# Transistors.net
KiCad netlist of a schematic drawn in Altium Designer
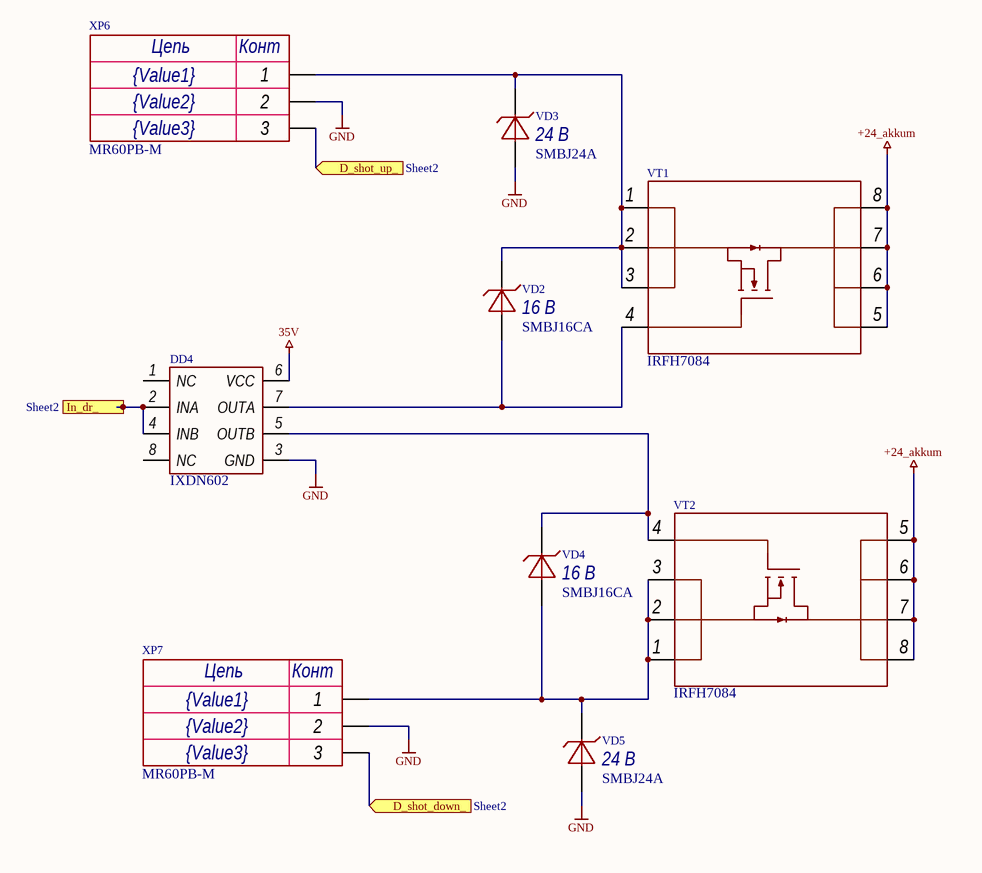
[diagram p0: Transistors.SchDoc]

(export (version "E")
  (design (tool "Eeschema 10.0.6"))
  (components
    (comp (ref "DD4")
      (value "IXDN602")
      (footprint "SOIC-8")
      (description "Двухканальный драйвер затвора для mosfet и igbt транзисторов")
      (libsource (lib "Hydrolib") (part "IXDN602"))
    )
    (comp (ref "VD2")
      (value "SMBJ16CA")
      (footprint "SMB")
      (description "Защитный диод двунаправленный 600Вт 16В")
      (fields (field (name "ALTIUM_VALUE") "16 В"))
      (libsource (lib "Hydrolib") (part "TVS_1_1dir"))
    )
    (comp (ref "VD3")
      (value "SMBJ24A")
      (footprint "SMB")
      (description "Защитный диод на 24 В, рассеиваемая мощность 600 Вт")
      (fields (field (name "ALTIUM_VALUE") "24 В"))
      (libsource (lib "Hydrolib") (part "TVS_1_1dir"))
    )
    (comp (ref "VD4")
      (value "SMBJ16CA")
      (footprint "SMB")
      (description "Защитный диод двунаправленный 600Вт 16В")
      (fields (field (name "ALTIUM_VALUE") "16 В"))
      (libsource (lib "Hydrolib") (part "TVS_1_1dir"))
    )
    (comp (ref "VD5")
      (value "SMBJ24A")
      (footprint "SMB")
      (description "Защитный диод на 24 В, рассеиваемая мощность 600 Вт")
      (fields (field (name "ALTIUM_VALUE") "24 В"))
      (libsource (lib "Hydrolib") (part "TVS_1_1dir"))
    )
    (comp (ref "VT1")
      (value "IRFH7084")
      (footprint "PQFN_5x6")
      (description "N-канальный MOSFET")
      (libsource (lib "") (part "MOSFET_N-channel_8pin_1"))
    )
    (comp (ref "VT2")
      (value "IRFH7084")
      (footprint "PQFN_5x6")
      (description "N-канальный MOSFET")
      (libsource (lib "Hydrolib") (part "MOSFET_N-channel_8pin"))
    )
    (comp (ref "XP6")
      (value "MR60PB-M")
      (footprint "MR60PB-M")
      (description "60 А (40 продолжительно), 3 контакта, прямой отец")
      (fields
        (field (name "VALUE3") "{Value3}")
        (field (name "VALUE2") "{Value2}")
        (field (name "VALUE1") "{Value1}")
      )
      (libsource (lib "Hydrolib") (part "Conn_3pin"))
    )
    (comp (ref "XP7")
      (value "MR60PB-M")
      (footprint "MR60PB-M")
      (description "60 А (40 продолжительно), 3 контакта, прямой отец")
      (fields
        (field (name "VALUE3") "{Value3}")
        (field (name "VALUE2") "{Value2}")
        (field (name "VALUE1") "{Value1}")
      )
      (libsource (lib "Hydrolib") (part "Conn_3pin"))
    )
  )
  (nets
    (net (code "1") (name "+24_akkum") (class "Default")
      (node (ref "VT1") (pin "5") (pinfunction "5_5") (pintype "passive"))
      (node (ref "VT1") (pin "6") (pinfunction "6_6") (pintype "passive"))
      (node (ref "VT1") (pin "7") (pinfunction "7_7") (pintype "passive"))
      (node (ref "VT1") (pin "8") (pinfunction "8_8") (pintype "passive"))
      (node (ref "VT2") (pin "5") (pinfunction "5_5") (pintype "passive"))
      (node (ref "VT2") (pin "6") (pinfunction "6_6") (pintype "passive"))
      (node (ref "VT2") (pin "7") (pinfunction "7_7") (pintype "passive"))
      (node (ref "VT2") (pin "8") (pinfunction "8_8") (pintype "passive"))
    )
    (net (code "2") (name "/D_shot_down_") (class "Default")
      (node (ref "XP7") (pin "3") (pinfunction "3_3") (pintype "passive"))
    )
    (net (code "3") (name "/D_shot_up_") (class "Default")
      (node (ref "XP6") (pin "3") (pinfunction "3_3") (pintype "passive"))
    )
    (net (code "4") (name "/In_dr_") (class "Default")
      (node (ref "DD4") (pin "2") (pinfunction "INA_2") (pintype "passive"))
      (node (ref "DD4") (pin "4") (pinfunction "INB_4") (pintype "passive"))
    )
    (net (code "5") (name "35V") (class "Default")
      (node (ref "DD4") (pin "6") (pinfunction "VCC_6") (pintype "passive"))
    )
    (net (code "6") (name "GND") (class "Default")
      (node (ref "DD4") (pin "3") (pinfunction "GND_3") (pintype "passive"))
      (node (ref "VD3") (pin "1") (pinfunction "1_1") (pintype "passive"))
      (node (ref "VD5") (pin "1") (pinfunction "1_1") (pintype "passive"))
      (node (ref "XP6") (pin "2") (pinfunction "2_2") (pintype "passive"))
      (node (ref "XP7") (pin "2") (pinfunction "2_2") (pintype "passive"))
    )
    (net (code "7") (name "Net-(DD4-OUTA)") (class "Default")
      (node (ref "DD4") (pin "7") (pinfunction "OUTA_7") (pintype "passive"))
      (node (ref "VD2") (pin "1") (pinfunction "1_1") (pintype "passive"))
      (node (ref "VT1") (pin "4") (pinfunction "4_4") (pintype "passive"))
    )
    (net (code "8") (name "Net-(DD4-OUTB)") (class "Default")
      (node (ref "DD4") (pin "5") (pinfunction "OUTB_5") (pintype "passive"))
      (node (ref "VD4") (pin "2") (pinfunction "2_2") (pintype "passive"))
      (node (ref "VT2") (pin "4") (pinfunction "4_4") (pintype "passive"))
    )
    (net (code "9") (name "Net-(VD2-Pad2)") (class "Default")
      (node (ref "VD2") (pin "2") (pinfunction "2_2") (pintype "passive"))
      (node (ref "VD3") (pin "2") (pinfunction "2_2") (pintype "passive"))
      (node (ref "VT1") (pin "1") (pinfunction "1_1") (pintype "passive"))
      (node (ref "VT1") (pin "2") (pinfunction "2_2") (pintype "passive"))
      (node (ref "VT1") (pin "3") (pinfunction "3_3") (pintype "passive"))
      (node (ref "XP6") (pin "1") (pinfunction "1_1") (pintype "passive"))
    )
    (net (code "10") (name "Net-(VD4-Pad1)") (class "Default")
      (node (ref "VD4") (pin "1") (pinfunction "1_1") (pintype "passive"))
      (node (ref "VD5") (pin "2") (pinfunction "2_2") (pintype "passive"))
      (node (ref "VT2") (pin "1") (pinfunction "1_1") (pintype "passive"))
      (node (ref "VT2") (pin "2") (pinfunction "2_2") (pintype "passive"))
      (node (ref "VT2") (pin "3") (pinfunction "3_3") (pintype "passive"))
      (node (ref "XP7") (pin "1") (pinfunction "1_1") (pintype "passive"))
    )
    (net (code "11") (name "unconnected-(DD4-NC-Pad1)") (class "Default")
      (node (ref "DD4") (pin "1") (pinfunction "NC_1") (pintype "passive"))
    )
    (net (code "12") (name "unconnected-(DD4-NC-Pad8)") (class "Default")
      (node (ref "DD4") (pin "8") (pinfunction "NC_8") (pintype "passive"))
    )
  )
)
